# bpod_stepper_1_1.net
KiCad netlist of a schematic drawn in EAGLE
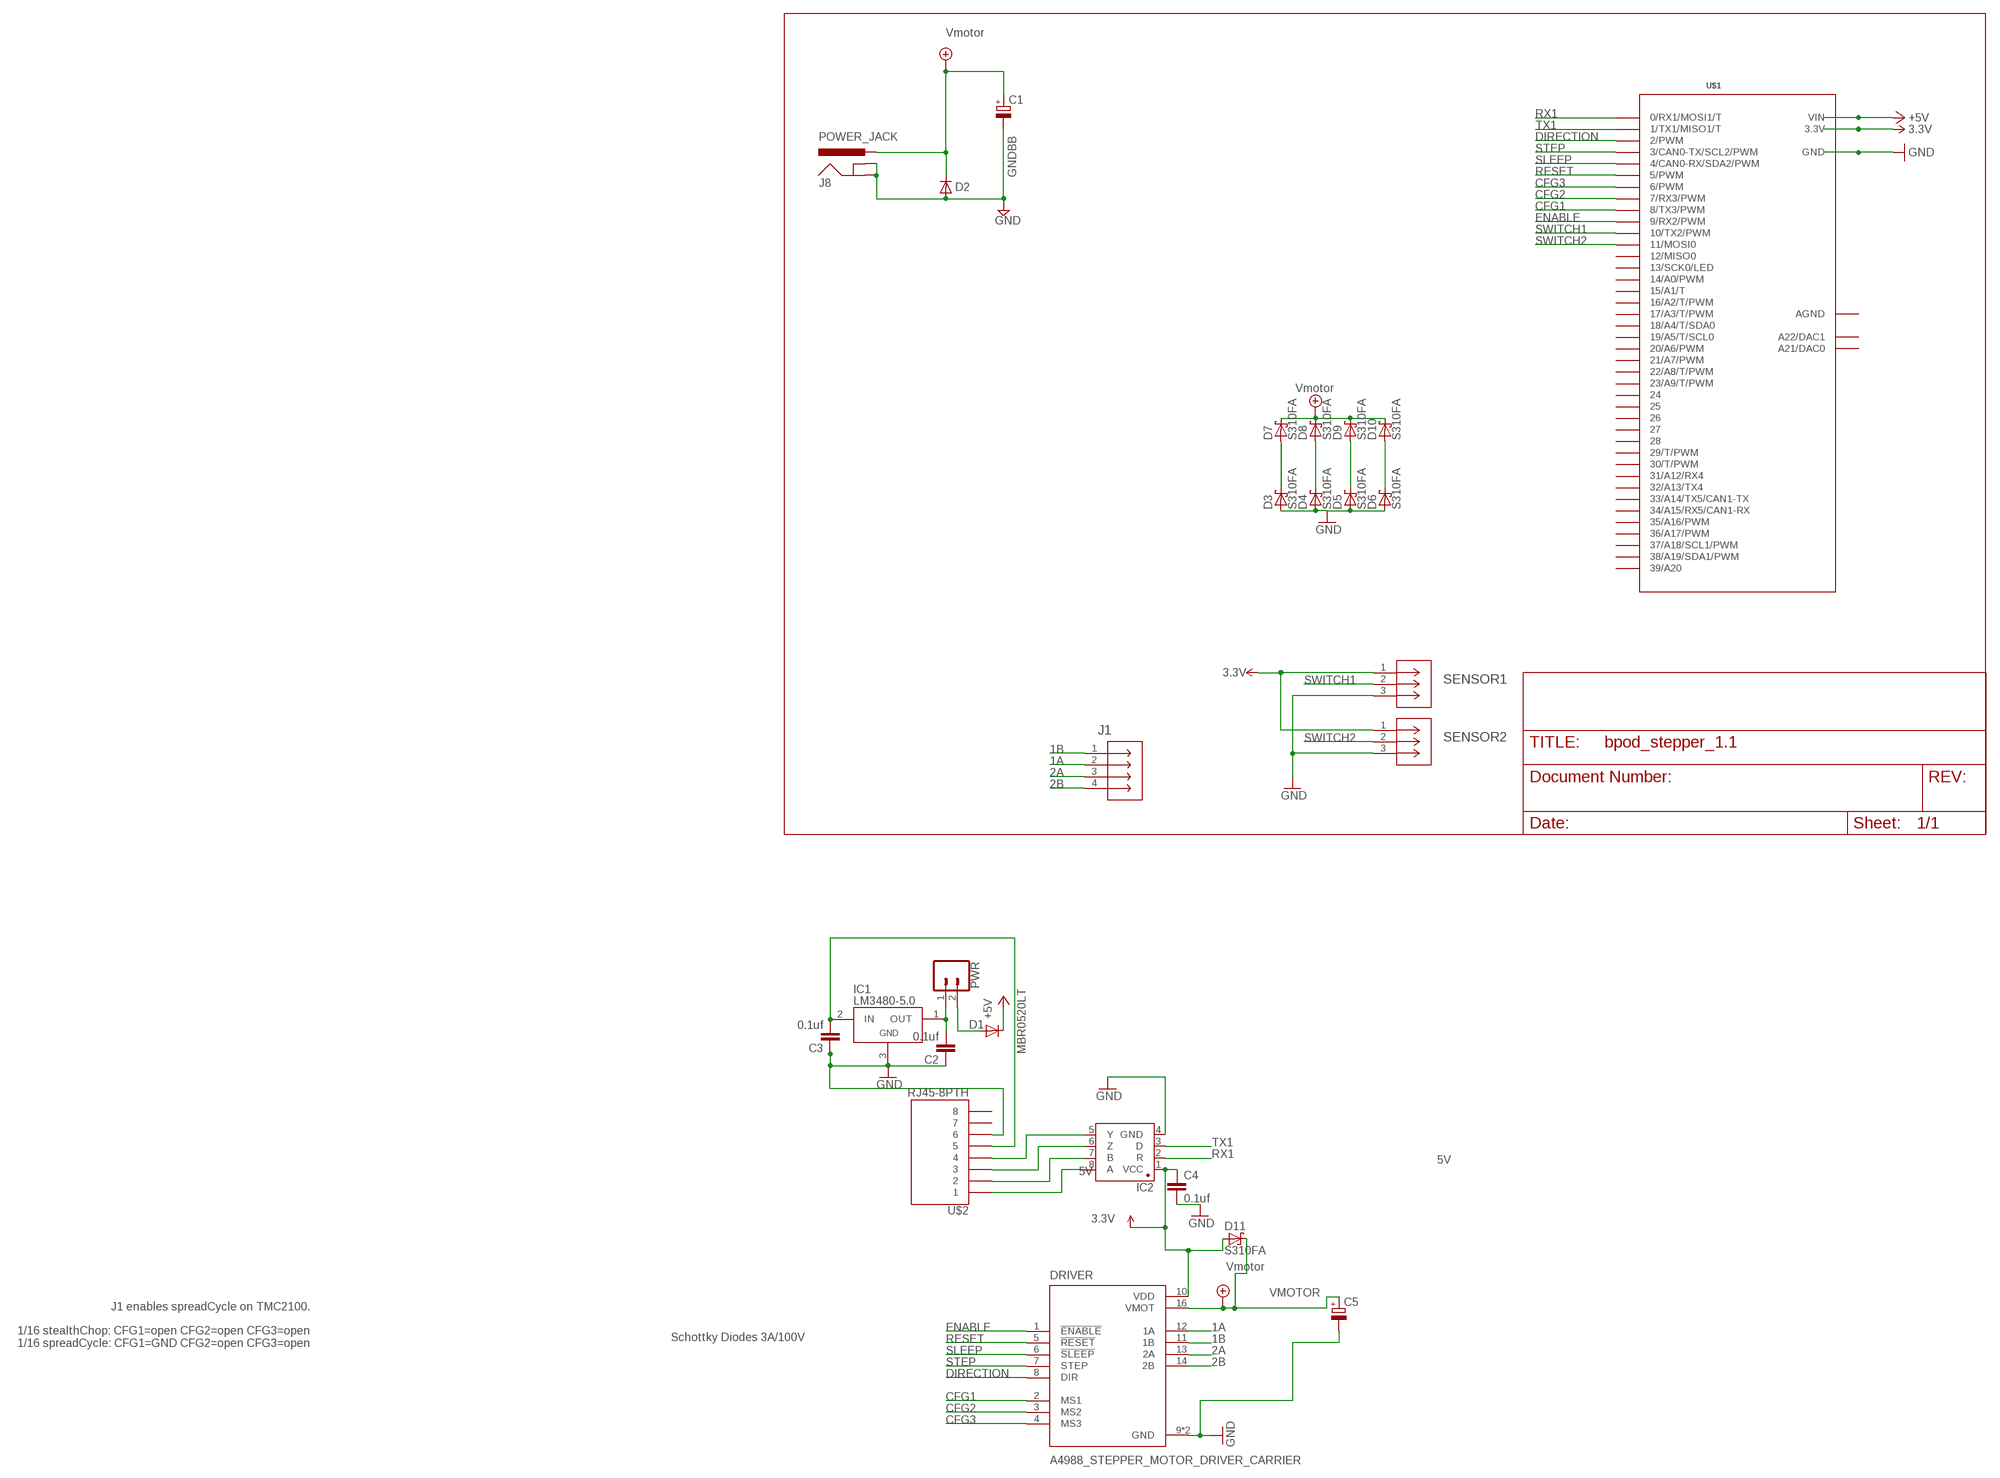
[diagram p0: schematic, sheet 1]

(export (version "E")
  (design (tool "Eeschema 10.0.6"))
  (components
    (comp (ref "C1")
      (value "CPOL-EUG")
      (footprint "eagle-import:PANASONIC_G")
      (libsource (lib "eagle-import") (part "CPOL-EUG"))
    )
    (comp (ref "C2")
      (value "0.1uf")
      (footprint "eagle-import:1206@1")
      (libsource (lib "eagle-import") (part "CAP1206"))
    )
    (comp (ref "C3")
      (value "0.1uf")
      (footprint "eagle-import:1206@1")
      (libsource (lib "eagle-import") (part "CAP1206"))
    )
    (comp (ref "C4")
      (value "0.1uf")
      (footprint "eagle-import:1206@1")
      (libsource (lib "eagle-import") (part "CAP1206"))
    )
    (comp (ref "C5")
      (value "CPOL-EUG")
      (footprint "eagle-import:PANASONIC_G")
      (libsource (lib "eagle-import") (part "CPOL-EUG"))
    )
    (comp (ref "D1")
      (value "MBR0520LT")
      (footprint "eagle-import:SOD123")
      (libsource (lib "eagle-import") (part "MBR0520LT"))
    )
    (comp (ref "D2")
      (value "DIODE-DO214AA")
      (footprint "eagle-import:DO214AA")
      (libsource (lib "eagle-import") (part "DIODE-DO214AA"))
    )
    (comp (ref "D3")
      (value "S310FA")
      (footprint "eagle-import:SOD123")
      (libsource (lib "eagle-import") (part "D_SCHOTTKY-SOD123"))
    )
    (comp (ref "D4")
      (value "S310FA")
      (footprint "eagle-import:SOD123")
      (libsource (lib "eagle-import") (part "D_SCHOTTKY-SOD123"))
    )
    (comp (ref "D5")
      (value "S310FA")
      (footprint "eagle-import:SOD123")
      (libsource (lib "eagle-import") (part "D_SCHOTTKY-SOD123"))
    )
    (comp (ref "D6")
      (value "S310FA")
      (footprint "eagle-import:SOD123")
      (libsource (lib "eagle-import") (part "D_SCHOTTKY-SOD123"))
    )
    (comp (ref "D7")
      (value "S310FA")
      (footprint "eagle-import:SOD123")
      (libsource (lib "eagle-import") (part "D_SCHOTTKY-SOD123"))
    )
    (comp (ref "D8")
      (value "S310FA")
      (footprint "eagle-import:SOD123")
      (libsource (lib "eagle-import") (part "D_SCHOTTKY-SOD123"))
    )
    (comp (ref "D9")
      (value "S310FA")
      (footprint "eagle-import:SOD123")
      (libsource (lib "eagle-import") (part "D_SCHOTTKY-SOD123"))
    )
    (comp (ref "D10")
      (value "S310FA")
      (footprint "eagle-import:SOD123")
      (libsource (lib "eagle-import") (part "D_SCHOTTKY-SOD123"))
    )
    (comp (ref "D11")
      (value "S310FA")
      (footprint "eagle-import:SOD123")
      (libsource (lib "eagle-import") (part "D_SCHOTTKY-SOD123"))
    )
    (comp (ref "DRIVER")
      (value "A4988_STEPPER_MOTOR_DRIVER_CARRIER")
      (footprint "eagle-import:MODULE_A4988_STEPPER_MOTOR_DRIVER_CARRIER")
      (fields (field (name "MF") "Pololu") (field (name "MP") "A4988 STEPPER MOTOR DRIVER CARRIER"))
      (libsource (lib "eagle-import") (part "A4988_STEPPER_MOTOR_DRIVER_CARRIER"))
    )
    (comp (ref "IC1")
      (value "LM3480-5.0")
      (footprint "eagle-import:SOT-23-3")
      (libsource (lib "eagle-import") (part "LM3480-5.0"))
    )
    (comp (ref "IC2")
      (value "SN65HVD31DR")
      (footprint "eagle-import:SO08")
      (libsource (lib "eagle-import") (part "SN65HVD31DR"))
    )
    (comp (ref "J1")
      (value "282841-4")
      (footprint "eagle-import:CONN4_282841-4_TEC")
      (fields (field (name "COPYRIGHT") "Copyright (C) 2018 Accelerated Designs. All rights reserved"))
      (libsource (lib "eagle-import") (part "282841-4"))
    )
    (comp (ref "J8")
      (value "POWER_JACK")
      (footprint "eagle-import:POWER_JACK_PTH")
      (libsource (lib "eagle-import") (part "POWER_JACK"))
    )
    (comp (ref "PWR")
      (value "CONN_02")
      (footprint "eagle-import:1X02")
      (libsource (lib "eagle-import") (part "CONN_02"))
    )
    (comp (ref "SENSOR1")
      (value "282834-3")
      (footprint "eagle-import:CONN_282834-3_TYC")
      (fields (field (name "COPYRIGHT") "Copyright (C) 2016 Accelerated Designs. All rights reserved"))
      (libsource (lib "eagle-import") (part "282834-3"))
    )
    (comp (ref "SENSOR2")
      (value "282834-3")
      (footprint "eagle-import:CONN_282834-3_TYC")
      (fields (field (name "COPYRIGHT") "Copyright (C) 2016 Accelerated Designs. All rights reserved"))
      (libsource (lib "eagle-import") (part "282834-3"))
    )
    (comp (ref "U$1")
      (value "TEENSY_3.6_DIL")
      (footprint "eagle-import:TEENSY_3.6_DIL")
      (libsource (lib "eagle-import") (part "TEENSY_3.6_DIL"))
    )
    (comp (ref "U$2")
      (value "RJ45-8PTH")
      (footprint "eagle-import:RJ45-8")
      (libsource (lib "eagle-import") (part "RJ45-8PTH"))
    )
  )
  (nets
    (net (code "1") (name "+5V") (class "Default")
      (node (ref "D1") (pin "C") (pinfunction "C_C") (pintype "passive"))
      (node (ref "U$1") (pin "VIN") (pinfunction "VIN_VIN") (pintype "power_in"))
    )
    (net (code "2") (name "/1A") (class "Default")
      (node (ref "D4") (pin "C") (pinfunction "C_C") (pintype "passive"))
      (node (ref "D8") (pin "A") (pinfunction "A_A") (pintype "passive"))
      (node (ref "DRIVER") (pin "12") (pinfunction "1A_12") (pintype "output"))
      (node (ref "J1") (pin "2") (pinfunction "2_2") (pintype "passive"))
    )
    (net (code "3") (name "/1B") (class "Default")
      (node (ref "D3") (pin "C") (pinfunction "C_C") (pintype "passive"))
      (node (ref "D7") (pin "A") (pinfunction "A_A") (pintype "passive"))
      (node (ref "DRIVER") (pin "11") (pinfunction "1B_11") (pintype "output"))
      (node (ref "J1") (pin "1") (pinfunction "1_1") (pintype "passive"))
    )
    (net (code "4") (name "/2A") (class "Default")
      (node (ref "D5") (pin "C") (pinfunction "C_C") (pintype "passive"))
      (node (ref "D9") (pin "A") (pinfunction "A_A") (pintype "passive"))
      (node (ref "DRIVER") (pin "13") (pinfunction "2A_13") (pintype "output"))
      (node (ref "J1") (pin "3") (pinfunction "3_3") (pintype "passive"))
    )
    (net (code "5") (name "/2B") (class "Default")
      (node (ref "D10") (pin "A") (pinfunction "A_A") (pintype "passive"))
      (node (ref "D6") (pin "C") (pinfunction "C_C") (pintype "passive"))
      (node (ref "DRIVER") (pin "14") (pinfunction "2B_14") (pintype "output"))
      (node (ref "J1") (pin "4") (pinfunction "4_4") (pintype "passive"))
    )
    (net (code "6") (name "/AGND") (class "Default")
      (node (ref "U$1") (pin "AGND") (pinfunction "AGND_AGND") (pintype "power_in"))
    )
    (net (code "7") (name "/CFG1") (class "Default")
      (node (ref "DRIVER") (pin "2") (pinfunction "MS1_2") (pintype "input"))
      (node (ref "U$1") (pin "8") (pinfunction "8/TX3/PWM_8") (pintype "bidirectional"))
    )
    (net (code "8") (name "/CFG2") (class "Default")
      (node (ref "DRIVER") (pin "3") (pinfunction "MS2_3") (pintype "input"))
      (node (ref "U$1") (pin "7") (pinfunction "7/RX3/PWM_7") (pintype "bidirectional"))
    )
    (net (code "9") (name "/CFG3") (class "Default")
      (node (ref "DRIVER") (pin "4") (pinfunction "MS3_4") (pintype "input"))
      (node (ref "U$1") (pin "6") (pinfunction "6/PWM_6") (pintype "bidirectional"))
    )
    (net (code "10") (name "/DIRECTION") (class "Default")
      (node (ref "DRIVER") (pin "8") (pinfunction "DIR_8") (pintype "input"))
      (node (ref "U$1") (pin "2") (pinfunction "2/PWM_2") (pintype "bidirectional"))
    )
    (net (code "11") (name "/ENABLE") (class "Default")
      (node (ref "DRIVER") (pin "1") (pinfunction "~{ENABLE}_1") (pintype "input"))
      (node (ref "U$1") (pin "9") (pinfunction "9/RX2/PWM_9") (pintype "bidirectional"))
    )
    (net (code "12") (name "/RESET") (class "Default")
      (node (ref "DRIVER") (pin "5") (pinfunction "~{RESET}_5") (pintype "input"))
      (node (ref "U$1") (pin "5") (pinfunction "5/PWM_5") (pintype "bidirectional"))
    )
    (net (code "13") (name "/RX1") (class "Default")
      (node (ref "IC2") (pin "2") (pinfunction "R_2") (pintype "bidirectional"))
      (node (ref "U$1") (pin "0") (pinfunction "0/RX1/MOSI1/T_0") (pintype "bidirectional"))
    )
    (net (code "14") (name "/SLEEP") (class "Default")
      (node (ref "DRIVER") (pin "6") (pinfunction "~{SLEEP}_6") (pintype "input"))
      (node (ref "U$1") (pin "4") (pinfunction "4/CAN0-RX/SDA2/PWM_4") (pintype "bidirectional"))
    )
    (net (code "15") (name "/STEP") (class "Default")
      (node (ref "DRIVER") (pin "7") (pinfunction "STEP_7") (pintype "input"))
      (node (ref "U$1") (pin "3") (pinfunction "3/CAN0-TX/SCL2/PWM_3") (pintype "bidirectional"))
    )
    (net (code "16") (name "/SWITCH1") (class "Default")
      (node (ref "SENSOR1") (pin "2") (pinfunction "2_2") (pintype "passive"))
      (node (ref "U$1") (pin "10") (pinfunction "10/TX2/PWM_10") (pintype "bidirectional"))
    )
    (net (code "17") (name "/SWITCH2") (class "Default")
      (node (ref "SENSOR2") (pin "2") (pinfunction "2_2") (pintype "passive"))
      (node (ref "U$1") (pin "11") (pinfunction "11/MOSI0_11") (pintype "bidirectional"))
    )
    (net (code "18") (name "/TX1") (class "Default")
      (node (ref "IC2") (pin "3") (pinfunction "D_3") (pintype "bidirectional"))
      (node (ref "U$1") (pin "1") (pinfunction "1/TX1/MISO1/T_1") (pintype "bidirectional"))
    )
    (net (code "19") (name "3.3V") (class "Default")
      (node (ref "C4") (pin "1") (pinfunction "1_1") (pintype "passive"))
      (node (ref "D11") (pin "A") (pinfunction "A_A") (pintype "passive"))
      (node (ref "DRIVER") (pin "10") (pinfunction "VDD_10") (pintype "power_in"))
      (node (ref "IC2") (pin "1") (pinfunction "VCC_1") (pintype "bidirectional"))
      (node (ref "SENSOR1") (pin "1") (pinfunction "1_1") (pintype "passive"))
      (node (ref "SENSOR2") (pin "1") (pinfunction "1_1") (pintype "passive"))
      (node (ref "U$1") (pin "3.3V") (pinfunction "3.3V_3.3V") (pintype "power_in"))
      (node (ref "U$1") (pin "3.3V3") (pinfunction "3.3V_3.3V3") (pintype "power_in"))
    )
    (net (code "20") (name "GND") (class "Default")
      (node (ref "C1") (pin "-") (pinfunction "-_-") (pintype "passive"))
      (node (ref "C2") (pin "1") (pinfunction "1_1") (pintype "passive"))
      (node (ref "C3") (pin "1") (pinfunction "1_1") (pintype "passive"))
      (node (ref "C4") (pin "2") (pinfunction "2_2") (pintype "passive"))
      (node (ref "C5") (pin "-") (pinfunction "-_-") (pintype "passive"))
      (node (ref "D2") (pin "A") (pinfunction "A_A") (pintype "passive"))
      (node (ref "D3") (pin "A") (pinfunction "A_A") (pintype "passive"))
      (node (ref "D4") (pin "A") (pinfunction "A_A") (pintype "passive"))
      (node (ref "D5") (pin "A") (pinfunction "A_A") (pintype "passive"))
      (node (ref "D6") (pin "A") (pinfunction "A_A") (pintype "passive"))
      (node (ref "DRIVER") (pin "15") (pinfunction "GND_15") (pintype "power_in"))
      (node (ref "DRIVER") (pin "9") (pinfunction "GND_9") (pintype "power_in"))
      (node (ref "IC1") (pin "3") (pinfunction "GND_3") (pintype "power_in"))
      (node (ref "IC2") (pin "4") (pinfunction "GND_4") (pintype "bidirectional"))
      (node (ref "J8") (pin "GND") (pinfunction "GND_GND") (pintype "bidirectional"))
      (node (ref "J8") (pin "GNDBREAK") (pinfunction "GNDBREAK_GNDBREAK") (pintype "bidirectional"))
      (node (ref "SENSOR1") (pin "3") (pinfunction "3_3") (pintype "passive"))
      (node (ref "SENSOR2") (pin "3") (pinfunction "3_3") (pintype "passive"))
      (node (ref "U$1") (pin "GND") (pinfunction "GND_GND") (pintype "power_in"))
      (node (ref "U$1") (pin "GND1") (pinfunction "GND_GND1") (pintype "power_in"))
      (node (ref "U$2") (pin "6") (pinfunction "6_6") (pintype "bidirectional"))
    )
    (net (code "21") (name "Net-(D1-PadA)") (class "Default")
      (node (ref "D1") (pin "A") (pinfunction "A_A") (pintype "passive"))
      (node (ref "PWR") (pin "2") (pinfunction "2_2") (pintype "passive"))
    )
    (net (code "22") (name "Net-(IC1-IN)") (class "Default")
      (node (ref "C3") (pin "2") (pinfunction "2_2") (pintype "passive"))
      (node (ref "IC1") (pin "2") (pinfunction "IN_2") (pintype "power_in"))
      (node (ref "U$2") (pin "5") (pinfunction "5_5") (pintype "bidirectional"))
    )
    (net (code "23") (name "Net-(IC1-OUT)") (class "Default")
      (node (ref "C2") (pin "2") (pinfunction "2_2") (pintype "passive"))
      (node (ref "IC1") (pin "1") (pinfunction "OUT_1") (pintype "power_in"))
      (node (ref "PWR") (pin "1") (pinfunction "1_1") (pintype "passive"))
    )
    (net (code "24") (name "Net-(IC2-A)") (class "Default")
      (node (ref "IC2") (pin "8") (pinfunction "A_8") (pintype "bidirectional"))
      (node (ref "U$2") (pin "1") (pinfunction "1_1") (pintype "bidirectional"))
    )
    (net (code "25") (name "Net-(IC2-B)") (class "Default")
      (node (ref "IC2") (pin "7") (pinfunction "B_7") (pintype "bidirectional"))
      (node (ref "U$2") (pin "2") (pinfunction "2_2") (pintype "bidirectional"))
    )
    (net (code "26") (name "Net-(IC2-Y)") (class "Default")
      (node (ref "IC2") (pin "5") (pinfunction "Y_5") (pintype "bidirectional"))
      (node (ref "U$2") (pin "4") (pinfunction "4_4") (pintype "bidirectional"))
    )
    (net (code "27") (name "Net-(IC2-Z)") (class "Default")
      (node (ref "IC2") (pin "6") (pinfunction "Z_6") (pintype "bidirectional"))
      (node (ref "U$2") (pin "3") (pinfunction "3_3") (pintype "bidirectional"))
    )
    (net (code "28") (name "Vmotor") (class "Default")
      (node (ref "C1") (pin "+") (pinfunction "+_+") (pintype "passive"))
      (node (ref "C5") (pin "+") (pinfunction "+_+") (pintype "passive"))
      (node (ref "D10") (pin "C") (pinfunction "C_C") (pintype "passive"))
      (node (ref "D11") (pin "C") (pinfunction "C_C") (pintype "passive"))
      (node (ref "D2") (pin "C") (pinfunction "C_C") (pintype "passive"))
      (node (ref "D7") (pin "C") (pinfunction "C_C") (pintype "passive"))
      (node (ref "D8") (pin "C") (pinfunction "C_C") (pintype "passive"))
      (node (ref "D9") (pin "C") (pinfunction "C_C") (pintype "passive"))
      (node (ref "DRIVER") (pin "16") (pinfunction "VMOT_16") (pintype "power_in"))
      (node (ref "J8") (pin "PWR") (pinfunction "PWR_PWR") (pintype "bidirectional"))
    )
    (net (code "29") (name "unconnected-(U$1-12{slash}MISO0-Pad12)") (class "Default")
      (node (ref "U$1") (pin "12") (pinfunction "12/MISO0_12") (pintype "bidirectional"))
    )
    (net (code "30") (name "unconnected-(U$1-13{slash}SCK0{slash}LED-Pad13)") (class "Default")
      (node (ref "U$1") (pin "13") (pinfunction "13/SCK0/LED_13") (pintype "bidirectional"))
    )
    (net (code "31") (name "unconnected-(U$1-14{slash}A0{slash}PWM-Pad14{slash}A0)") (class "Default")
      (node (ref "U$1") (pin "14/A0") (pinfunction "14/A0/PWM_14/A0") (pintype "bidirectional"))
    )
    (net (code "32") (name "unconnected-(U$1-15{slash}A1{slash}T-Pad15{slash}A1)") (class "Default")
      (node (ref "U$1") (pin "15/A1") (pinfunction "15/A1/T_15/A1") (pintype "bidirectional"))
    )
    (net (code "33") (name "unconnected-(U$1-16{slash}A2{slash}T{slash}PWM-Pad16{slash}A2)") (class "Default")
      (node (ref "U$1") (pin "16/A2") (pinfunction "16/A2/T/PWM_16/A2") (pintype "bidirectional"))
    )
    (net (code "34") (name "unconnected-(U$1-17{slash}A3{slash}T{slash}PWM-Pad17{slash}A3)") (class "Default")
      (node (ref "U$1") (pin "17/A3") (pinfunction "17/A3/T/PWM_17/A3") (pintype "bidirectional"))
    )
    (net (code "35") (name "unconnected-(U$1-18{slash}A4{slash}T{slash}SDA0-Pad18{slash}A4)") (class "Default")
      (node (ref "U$1") (pin "18/A4") (pinfunction "18/A4/T/SDA0_18/A4") (pintype "bidirectional"))
    )
    (net (code "36") (name "unconnected-(U$1-19{slash}A5{slash}T{slash}SCL0-Pad19{slash}A5)") (class "Default")
      (node (ref "U$1") (pin "19/A5") (pinfunction "19/A5/T/SCL0_19/A5") (pintype "bidirectional"))
    )
    (net (code "37") (name "unconnected-(U$1-20{slash}A6{slash}PWM-Pad20{slash}A6)") (class "Default")
      (node (ref "U$1") (pin "20/A6") (pinfunction "20/A6/PWM_20/A6") (pintype "bidirectional"))
    )
    (net (code "38") (name "unconnected-(U$1-21{slash}A7{slash}PWM-Pad21{slash}A7)") (class "Default")
      (node (ref "U$1") (pin "21/A7") (pinfunction "21/A7/PWM_21/A7") (pintype "bidirectional"))
    )
    (net (code "39") (name "unconnected-(U$1-22{slash}A8{slash}T{slash}PWM-Pad22{slash}A8)") (class "Default")
      (node (ref "U$1") (pin "22/A8") (pinfunction "22/A8/T/PWM_22/A8") (pintype "bidirectional"))
    )
    (net (code "40") (name "unconnected-(U$1-23{slash}A9{slash}T{slash}PWM-Pad23{slash}A9)") (class "Default")
      (node (ref "U$1") (pin "23/A9") (pinfunction "23/A9/T/PWM_23/A9") (pintype "bidirectional"))
    )
    (net (code "41") (name "unconnected-(U$1-29{slash}T{slash}PWM-Pad29)") (class "Default")
      (node (ref "U$1") (pin "29") (pinfunction "29/T/PWM_29") (pintype "bidirectional"))
    )
    (net (code "42") (name "unconnected-(U$1-30{slash}T{slash}PWM-Pad30)") (class "Default")
      (node (ref "U$1") (pin "30") (pinfunction "30/T/PWM_30") (pintype "bidirectional"))
    )
    (net (code "43") (name "unconnected-(U$1-31{slash}A12{slash}RX4-Pad31{slash}A12)") (class "Default")
      (node (ref "U$1") (pin "31/A12") (pinfunction "31/A12/RX4_31/A12") (pintype "bidirectional"))
    )
    (net (code "44") (name "unconnected-(U$1-32{slash}A13{slash}TX4-Pad32{slash}A13)") (class "Default")
      (node (ref "U$1") (pin "32/A13") (pinfunction "32/A13/TX4_32/A13") (pintype "bidirectional"))
    )
    (net (code "45") (name "unconnected-(U$1-33{slash}A14{slash}TX5{slash}CAN1-TX-Pad33{slash}A14)") (class "Default")
      (node (ref "U$1") (pin "33/A14") (pinfunction "33/A14/TX5/CAN1-TX_33/A14") (pintype "bidirectional"))
    )
    (net (code "46") (name "unconnected-(U$1-34{slash}A15{slash}RX5{slash}CAN1-RX-Pad34{slash}A15)") (class "Default")
      (node (ref "U$1") (pin "34/A15") (pinfunction "34/A15/RX5/CAN1-RX_34/A15") (pintype "bidirectional"))
    )
    (net (code "47") (name "unconnected-(U$1-35{slash}A16{slash}PWM-Pad35{slash}A16)") (class "Default")
      (node (ref "U$1") (pin "35/A16") (pinfunction "35/A16/PWM_35/A16") (pintype "bidirectional"))
    )
    (net (code "48") (name "unconnected-(U$1-36{slash}A17{slash}PWM-Pad36{slash}A17)") (class "Default")
      (node (ref "U$1") (pin "36/A17") (pinfunction "36/A17/PWM_36/A17") (pintype "bidirectional"))
    )
    (net (code "49") (name "unconnected-(U$1-37{slash}A18{slash}SCL1{slash}PWM-Pad37{slash}A18)") (class "Default")
      (node (ref "U$1") (pin "37/A18") (pinfunction "37/A18/SCL1/PWM_37/A18") (pintype "bidirectional"))
    )
    (net (code "50") (name "unconnected-(U$1-38{slash}A19{slash}SDA1{slash}PWM-Pad38{slash}A19)") (class "Default")
      (node (ref "U$1") (pin "38/A19") (pinfunction "38/A19/SDA1/PWM_38/A19") (pintype "bidirectional"))
    )
    (net (code "51") (name "unconnected-(U$1-A21{slash}DAC0-PadA21)") (class "Default")
      (node (ref "U$1") (pin "A21") (pinfunction "A21/DAC0_A21") (pintype "bidirectional"))
    )
    (net (code "52") (name "unconnected-(U$1-A22{slash}DAC1-PadA22)") (class "Default")
      (node (ref "U$1") (pin "A22") (pinfunction "A22/DAC1_A22") (pintype "bidirectional"))
    )
    (net (code "53") (name "unconnected-(U$1-Pad24)") (class "Default")
      (node (ref "U$1") (pin "24") (pinfunction "24_24") (pintype "bidirectional"))
    )
    (net (code "54") (name "unconnected-(U$1-Pad25)") (class "Default")
      (node (ref "U$1") (pin "25") (pinfunction "25_25") (pintype "bidirectional"))
    )
    (net (code "55") (name "unconnected-(U$1-Pad26)") (class "Default")
      (node (ref "U$1") (pin "26") (pinfunction "26_26") (pintype "bidirectional"))
    )
    (net (code "56") (name "unconnected-(U$1-Pad27)") (class "Default")
      (node (ref "U$1") (pin "27") (pinfunction "27_27") (pintype "bidirectional"))
    )
    (net (code "57") (name "unconnected-(U$1-Pad28)") (class "Default")
      (node (ref "U$1") (pin "28") (pinfunction "28_28") (pintype "bidirectional"))
    )
    (net (code "58") (name "unconnected-(U$1-Pad39{slash}A20)") (class "Default")
      (node (ref "U$1") (pin "39/A20") (pinfunction "39/A20_39/A20") (pintype "bidirectional"))
    )
    (net (code "59") (name "unconnected-(U$2-Pad7)") (class "Default")
      (node (ref "U$2") (pin "7") (pinfunction "7_7") (pintype "bidirectional"))
    )
    (net (code "60") (name "unconnected-(U$2-Pad8)") (class "Default")
      (node (ref "U$2") (pin "8") (pinfunction "8_8") (pintype "bidirectional"))
    )
  )
)
